# LM2596_DC_TO_DC_schematic.net
KiCad netlist of a schematic drawn in Altium Designer
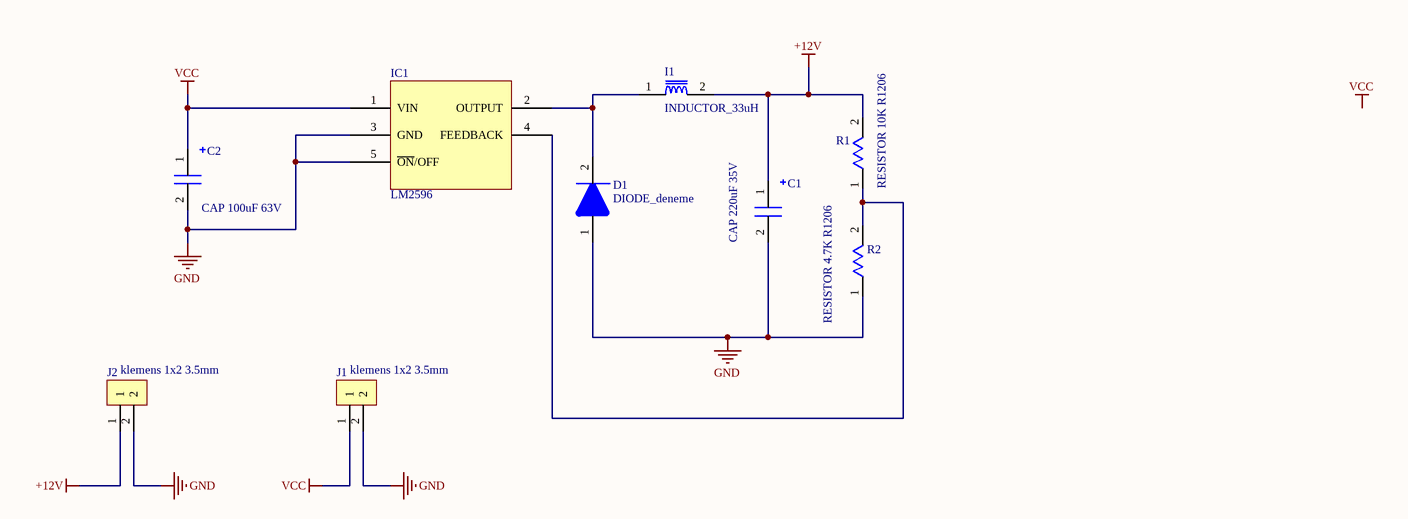
[diagram p0: LM2596_DC_TO_DC_schematic.SchDoc]

(export (version "E")
  (design (tool "Eeschema 10.0.6"))
  (components
    (comp (ref "C1")
      (value "CAP 220uF 35V")
      (footprint "CAPACITOR")
      (libsource (lib "LM2596_DC_TO_DC_Schematiclibrary1") (part "CAP 220uF 35V"))
    )
    (comp (ref "C2")
      (value "CAP 100uF 63V")
      (footprint "CAPACITOR")
      (description "CAPACITOR")
      (libsource (lib "LM2596_DC_TO_DC_Schematiclibrary1") (part "CAP 100uF 63V"))
    )
    (comp (ref "D1")
      (value "DIODE_deneme")
      (footprint "DIODE_deneme")
      (description "diode deneme yaptık kafamıza göre")
      (libsource (lib "LM2596_DC_TO_DC_Schematiclibrary1") (part "DIODE_deneme"))
    )
    (comp (ref "I1")
      (value "INDUCTOR_33uH")
      (footprint "SRR1280_Inductor")
      (description "INDUCTOR_33uH_SRR1280")
      (libsource (lib "LM2596_DC_TO_DC_Schematiclibrary1") (part "INDUCTOR_33uH"))
    )
    (comp (ref "IC1")
      (value "LM2596")
      (footprint "LM2596_DC_TO_DC_PcbLibrary1:D2PAK")
      (description "REGULATOR  DC TO DC ,DUCK CONVERTER")
      (libsource (lib "LM2596_DC_TO_DC_Schematiclibrary1") (part "LM2596"))
    )
    (comp (ref "J1")
      (value "klemens 1x2 3.5mm")
      (footprint "klemens 1x2 3.5mm")
      (description "Klemens 1x2 3.5mm")
      (libsource (lib "LM2596_DC_TO_DC_Schematiclibrary1") (part "klemens 1x2 3.5mm"))
    )
    (comp (ref "J2")
      (value "klemens 1x2 3.5mm")
      (footprint "klemens 1x2 3.5mm")
      (description "Klemens 1x2 3.5mm")
      (libsource (lib "LM2596_DC_TO_DC_Schematiclibrary1") (part "klemens 1x2 3.5mm"))
    )
    (comp (ref "R1")
      (value "RESISTOR 10K R1206")
      (footprint "R1206 RESISTER")
      (description "R1206 RESISTER")
      (libsource (lib "LM2596_DC_TO_DC_Schematiclibrary1") (part "RESISTOR 10K R1206"))
    )
    (comp (ref "R2")
      (value "RESISTOR 4.7K R1206")
      (footprint "R1206 RESISTER")
      (description "R1206 RESISTER")
      (libsource (lib "LM2596_DC_TO_DC_Schematiclibrary1") (part "RESISTOR 4.7K R1206"))
    )
  )
  (nets
    (net (code "1") (name "+12V") (class "Default")
      (node (ref "C1") (pin "1") (pinfunction "1_1") (pintype "passive"))
      (node (ref "I1") (pin "2") (pinfunction "2_2") (pintype "passive"))
      (node (ref "J2") (pin "1") (pinfunction "1_1") (pintype "passive"))
      (node (ref "R1") (pin "2") (pinfunction "2_2") (pintype "passive"))
    )
    (net (code "2") (name "GND") (class "Default")
      (node (ref "C1") (pin "2") (pinfunction "2_2") (pintype "passive"))
      (node (ref "C2") (pin "2") (pinfunction "2_2") (pintype "passive"))
      (node (ref "D1") (pin "1") (pinfunction "1_1") (pintype "passive"))
      (node (ref "IC1") (pin "3") (pinfunction "GND_3") (pintype "passive"))
      (node (ref "IC1") (pin "5") (pinfunction "~{ON}/OFF_5") (pintype "passive"))
      (node (ref "J1") (pin "2") (pinfunction "2_2") (pintype "passive"))
      (node (ref "J2") (pin "2") (pinfunction "2_2") (pintype "passive"))
      (node (ref "R2") (pin "1") (pinfunction "1_1") (pintype "passive"))
    )
    (net (code "3") (name "Net-(IC1-FEEDBACK)") (class "Default")
      (node (ref "IC1") (pin "4") (pinfunction "FEEDBACK_4") (pintype "passive"))
      (node (ref "R1") (pin "1") (pinfunction "1_1") (pintype "passive"))
      (node (ref "R2") (pin "2") (pinfunction "2_2") (pintype "passive"))
    )
    (net (code "4") (name "Net-(IC1-OUTPUT)") (class "Default")
      (node (ref "D1") (pin "2") (pinfunction "2_2") (pintype "passive"))
      (node (ref "I1") (pin "1") (pinfunction "1_1") (pintype "passive"))
      (node (ref "IC1") (pin "2") (pinfunction "OUTPUT_2") (pintype "passive"))
    )
    (net (code "5") (name "VCC") (class "Default")
      (node (ref "C2") (pin "1") (pinfunction "1_1") (pintype "passive"))
      (node (ref "IC1") (pin "1") (pinfunction "VIN_1") (pintype "passive"))
      (node (ref "J1") (pin "1") (pinfunction "1_1") (pintype "passive"))
    )
  )
)
